# Servorino.net
KiCad netlist of a schematic drawn in EAGLE
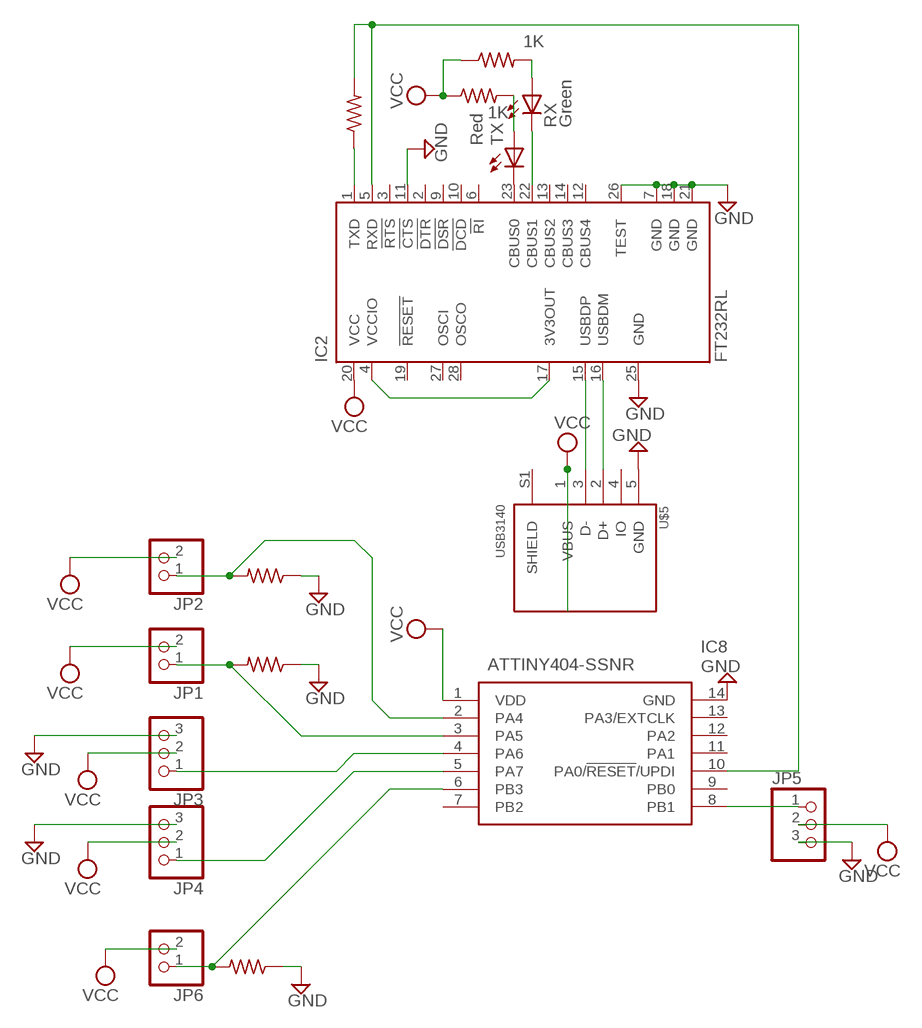
[diagram p0: schematic, sheet 1]

(export (version "E")
  (design (tool "Eeschema 10.0.6"))
  (components
    (comp (ref "IC2")
      (value "FT232RL")
      (footprint "eagle-import:SSOP28")
      (libsource (lib "eagle-import") (part "FT232RL"))
    )
    (comp (ref "IC8")
      (value "ATTINY404-SSNR")
      (footprint "eagle-import:SOIC127P600X175-14N")
      (fields (field (name "MOUSER_PART_NUMBER") "556-ATTINY404-SSNR"))
      (libsource (lib "eagle-import") (part "ATTINY404-SSNR"))
    )
    (comp (ref "JP1")
      (value "PINHD-1X2")
      (footprint "eagle-import:1X02")
      (libsource (lib "eagle-import") (part "PINHD-1X2"))
    )
    (comp (ref "JP2")
      (value "PINHD-1X2")
      (footprint "eagle-import:1X02")
      (libsource (lib "eagle-import") (part "PINHD-1X2"))
    )
    (comp (ref "JP3")
      (value "PINHD-1X3")
      (footprint "eagle-import:1X03")
      (libsource (lib "eagle-import") (part "PINHD-1X3"))
    )
    (comp (ref "JP4")
      (value "PINHD-1X3")
      (footprint "eagle-import:1X03")
      (libsource (lib "eagle-import") (part "PINHD-1X3"))
    )
    (comp (ref "JP5")
      (value "PINHD-1X3")
      (footprint "eagle-import:1X03")
      (libsource (lib "eagle-import") (part "PINHD-1X3"))
    )
    (comp (ref "JP6")
      (value "PINHD-1X2")
      (footprint "eagle-import:1X02")
      (libsource (lib "eagle-import") (part "PINHD-1X2"))
    )
    (comp (ref "R1")
      (value "470")
      (footprint "eagle-import:R0805")
      (libsource (lib "eagle-import") (part "R-US_R0805"))
    )
    (comp (ref "R2")
      (value "1K")
      (footprint "eagle-import:R0805")
      (libsource (lib "eagle-import") (part "R-US_R0805"))
    )
    (comp (ref "R3")
      (value "1K")
      (footprint "eagle-import:R0805")
      (libsource (lib "eagle-import") (part "R-US_R0805"))
    )
    (comp (ref "R4")
      (value "470")
      (footprint "eagle-import:R0805")
      (libsource (lib "eagle-import") (part "R-US_R0805"))
    )
    (comp (ref "R5")
      (value "470")
      (footprint "eagle-import:R0805")
      (libsource (lib "eagle-import") (part "R-US_R0805"))
    )
    (comp (ref "R6")
      (value "470")
      (footprint "eagle-import:R0805")
      (libsource (lib "eagle-import") (part "R-US_R0805"))
    )
    (comp (ref "RX")
      (value "Green")
      (footprint "eagle-import:CHIP-LED0805")
      (libsource (lib "eagle-import") (part "LEDCHIP-LED0805"))
    )
    (comp (ref "TX")
      (value "Red")
      (footprint "eagle-import:CHIP-LED0805")
      (libsource (lib "eagle-import") (part "LEDCHIP-LED0805"))
    )
    (comp (ref "U$5")
      (value "USB3140")
      (footprint "eagle-import:USB3140-30-0170-0-C")
      (libsource (lib "eagle-import") (part "USB3140"))
    )
  )
  (nets
    (net (code "1") (name "GND") (class "Default")
      (node (ref "IC2") (pin "11") (pinfunction "~{CTS}_11") (pintype "input"))
      (node (ref "IC2") (pin "18") (pinfunction "GND_18") (pintype "power_in"))
      (node (ref "IC2") (pin "21") (pinfunction "GND_21") (pintype "power_in"))
      (node (ref "IC2") (pin "25") (pinfunction "GND_25") (pintype "power_in"))
      (node (ref "IC2") (pin "26") (pinfunction "TEST_26") (pintype "input"))
      (node (ref "IC2") (pin "7") (pinfunction "GND_7") (pintype "power_in"))
      (node (ref "IC8") (pin "14") (pinfunction "GND_14") (pintype "bidirectional"))
      (node (ref "JP3") (pin "3") (pinfunction "3_3") (pintype "passive"))
      (node (ref "JP4") (pin "3") (pinfunction "3_3") (pintype "passive"))
      (node (ref "JP5") (pin "3") (pinfunction "3_3") (pintype "passive"))
      (node (ref "R4") (pin "1") (pinfunction "1_1") (pintype "passive"))
      (node (ref "R5") (pin "1") (pinfunction "1_1") (pintype "passive"))
      (node (ref "R6") (pin "1") (pinfunction "1_1") (pintype "passive"))
      (node (ref "U$5") (pin "5") (pinfunction "GND_5") (pintype "passive"))
    )
    (net (code "2") (name "Net-(IC2-3V3OUT)") (class "Default")
      (node (ref "IC2") (pin "17") (pinfunction "3V3OUT_17") (pintype "output"))
      (node (ref "IC2") (pin "4") (pinfunction "VCCIO_4") (pintype "power_in"))
    )
    (net (code "3") (name "Net-(IC2-CBUS0)") (class "Default")
      (node (ref "IC2") (pin "23") (pinfunction "CBUS0_23") (pintype "bidirectional"))
      (node (ref "TX") (pin "C") (pinfunction "C_C") (pintype "passive"))
    )
    (net (code "4") (name "Net-(IC2-CBUS1)") (class "Default")
      (node (ref "IC2") (pin "22") (pinfunction "CBUS1_22") (pintype "bidirectional"))
      (node (ref "RX") (pin "C") (pinfunction "C_C") (pintype "passive"))
    )
    (net (code "5") (name "Net-(IC2-RXD)") (class "Default")
      (node (ref "IC2") (pin "5") (pinfunction "RXD_5") (pintype "input"))
      (node (ref "IC8") (pin "10") (pinfunction "PA0/~{RESET}/UPDI_10") (pintype "bidirectional"))
      (node (ref "R1") (pin "2") (pinfunction "2_2") (pintype "passive"))
    )
    (net (code "6") (name "Net-(IC2-TXD)") (class "Default")
      (node (ref "IC2") (pin "1") (pinfunction "TXD_1") (pintype "output"))
      (node (ref "R1") (pin "1") (pinfunction "1_1") (pintype "passive"))
    )
    (net (code "7") (name "Net-(IC2-USBDM)") (class "Default")
      (node (ref "IC2") (pin "16") (pinfunction "USBDM_16") (pintype "bidirectional"))
      (node (ref "U$5") (pin "2") (pinfunction "D+_2") (pintype "passive"))
    )
    (net (code "8") (name "Net-(IC2-USBDP)") (class "Default")
      (node (ref "IC2") (pin "15") (pinfunction "USBDP_15") (pintype "bidirectional"))
      (node (ref "U$5") (pin "3") (pinfunction "D-_3") (pintype "passive"))
    )
    (net (code "9") (name "Net-(IC8-PA4)") (class "Default")
      (node (ref "IC8") (pin "2") (pinfunction "PA4_2") (pintype "bidirectional"))
      (node (ref "JP2") (pin "1") (pinfunction "1_1") (pintype "passive"))
      (node (ref "R6") (pin "2") (pinfunction "2_2") (pintype "passive"))
    )
    (net (code "10") (name "Net-(IC8-PA5)") (class "Default")
      (node (ref "IC8") (pin "3") (pinfunction "PA5_3") (pintype "bidirectional"))
      (node (ref "JP1") (pin "1") (pinfunction "1_1") (pintype "passive"))
      (node (ref "R5") (pin "2") (pinfunction "2_2") (pintype "passive"))
    )
    (net (code "11") (name "Net-(IC8-PA6)") (class "Default")
      (node (ref "IC8") (pin "4") (pinfunction "PA6_4") (pintype "bidirectional"))
      (node (ref "JP3") (pin "1") (pinfunction "1_1") (pintype "passive"))
    )
    (net (code "12") (name "Net-(IC8-PA7)") (class "Default")
      (node (ref "IC8") (pin "5") (pinfunction "PA7_5") (pintype "bidirectional"))
      (node (ref "JP4") (pin "1") (pinfunction "1_1") (pintype "passive"))
    )
    (net (code "13") (name "Net-(IC8-PB1)") (class "Default")
      (node (ref "IC8") (pin "8") (pinfunction "PB1_8") (pintype "bidirectional"))
      (node (ref "JP5") (pin "1") (pinfunction "1_1") (pintype "passive"))
    )
    (net (code "14") (name "Net-(IC8-PB3)") (class "Default")
      (node (ref "IC8") (pin "6") (pinfunction "PB3_6") (pintype "bidirectional"))
      (node (ref "JP6") (pin "1") (pinfunction "1_1") (pintype "passive"))
      (node (ref "R4") (pin "2") (pinfunction "2_2") (pintype "passive"))
    )
    (net (code "15") (name "Net-(R2-Pad2)") (class "Default")
      (node (ref "R2") (pin "2") (pinfunction "2_2") (pintype "passive"))
      (node (ref "RX") (pin "A") (pinfunction "A_A") (pintype "passive"))
    )
    (net (code "16") (name "Net-(R3-Pad2)") (class "Default")
      (node (ref "R3") (pin "2") (pinfunction "2_2") (pintype "passive"))
      (node (ref "TX") (pin "A") (pinfunction "A_A") (pintype "passive"))
    )
    (net (code "17") (name "VCC") (class "Default")
      (node (ref "IC2") (pin "20") (pinfunction "VCC_20") (pintype "power_in"))
      (node (ref "IC8") (pin "1") (pinfunction "VDD_1") (pintype "bidirectional"))
      (node (ref "JP1") (pin "2") (pinfunction "2_2") (pintype "passive"))
      (node (ref "JP2") (pin "2") (pinfunction "2_2") (pintype "passive"))
      (node (ref "JP3") (pin "2") (pinfunction "2_2") (pintype "passive"))
      (node (ref "JP4") (pin "2") (pinfunction "2_2") (pintype "passive"))
      (node (ref "JP5") (pin "2") (pinfunction "2_2") (pintype "passive"))
      (node (ref "JP6") (pin "2") (pinfunction "2_2") (pintype "passive"))
      (node (ref "R2") (pin "1") (pinfunction "1_1") (pintype "passive"))
      (node (ref "R3") (pin "1") (pinfunction "1_1") (pintype "passive"))
      (node (ref "U$5") (pin "1") (pinfunction "VBUS_1") (pintype "passive"))
    )
    (net (code "18") (name "unconnected-(IC2-CBUS2-Pad13)") (class "Default")
      (node (ref "IC2") (pin "13") (pinfunction "CBUS2_13") (pintype "bidirectional"))
    )
    (net (code "19") (name "unconnected-(IC2-CBUS3-Pad14)") (class "Default")
      (node (ref "IC2") (pin "14") (pinfunction "CBUS3_14") (pintype "bidirectional"))
    )
    (net (code "20") (name "unconnected-(IC2-CBUS4-Pad12)") (class "Default")
      (node (ref "IC2") (pin "12") (pinfunction "CBUS4_12") (pintype "bidirectional"))
    )
    (net (code "21") (name "unconnected-(IC2-OSCI-Pad27)") (class "Default")
      (node (ref "IC2") (pin "27") (pinfunction "OSCI_27") (pintype "input"))
    )
    (net (code "22") (name "unconnected-(IC2-OSCO-Pad28)") (class "Default")
      (node (ref "IC2") (pin "28") (pinfunction "OSCO_28") (pintype "output"))
    )
    (net (code "23") (name "unconnected-(IC2-~{DCD}-Pad10)") (class "Default")
      (node (ref "IC2") (pin "10") (pinfunction "~{DCD}_10") (pintype "input"))
    )
    (net (code "24") (name "unconnected-(IC2-~{DSR}-Pad9)") (class "Default")
      (node (ref "IC2") (pin "9") (pinfunction "~{DSR}_9") (pintype "input"))
    )
    (net (code "25") (name "unconnected-(IC2-~{DTR}-Pad2)") (class "Default")
      (node (ref "IC2") (pin "2") (pinfunction "~{DTR}_2") (pintype "output"))
    )
    (net (code "26") (name "unconnected-(IC2-~{RESET}-Pad19)") (class "Default")
      (node (ref "IC2") (pin "19") (pinfunction "~{RESET}_19") (pintype "input"))
    )
    (net (code "27") (name "unconnected-(IC2-~{RI}-Pad6)") (class "Default")
      (node (ref "IC2") (pin "6") (pinfunction "~{RI}_6") (pintype "input"))
    )
    (net (code "28") (name "unconnected-(IC2-~{RTS}-Pad3)") (class "Default")
      (node (ref "IC2") (pin "3") (pinfunction "~{RTS}_3") (pintype "output"))
    )
    (net (code "29") (name "unconnected-(IC8-PA1-Pad11)") (class "Default")
      (node (ref "IC8") (pin "11") (pinfunction "PA1_11") (pintype "bidirectional"))
    )
    (net (code "30") (name "unconnected-(IC8-PA2-Pad12)") (class "Default")
      (node (ref "IC8") (pin "12") (pinfunction "PA2_12") (pintype "bidirectional"))
    )
    (net (code "31") (name "unconnected-(IC8-PA3{slash}EXTCLK-Pad13)") (class "Default")
      (node (ref "IC8") (pin "13") (pinfunction "PA3/EXTCLK_13") (pintype "bidirectional"))
    )
    (net (code "32") (name "unconnected-(IC8-PB0-Pad9)") (class "Default")
      (node (ref "IC8") (pin "9") (pinfunction "PB0_9") (pintype "bidirectional"))
    )
    (net (code "33") (name "unconnected-(IC8-PB2-Pad7)") (class "Default")
      (node (ref "IC8") (pin "7") (pinfunction "PB2_7") (pintype "bidirectional"))
    )
    (net (code "34") (name "unconnected-(U$5-IO-Pad4)") (class "Default")
      (node (ref "U$5") (pin "4") (pinfunction "IO_4") (pintype "passive"))
    )
    (net (code "35") (name "unconnected-(U$5-SHIELD-PadS1)") (class "Default")
      (node (ref "U$5") (pin "S1") (pinfunction "SHIELD_S1") (pintype "passive"))
    )
  )
)
